# SPLED-01.net
KiCad netlist of a schematic drawn in EAGLE
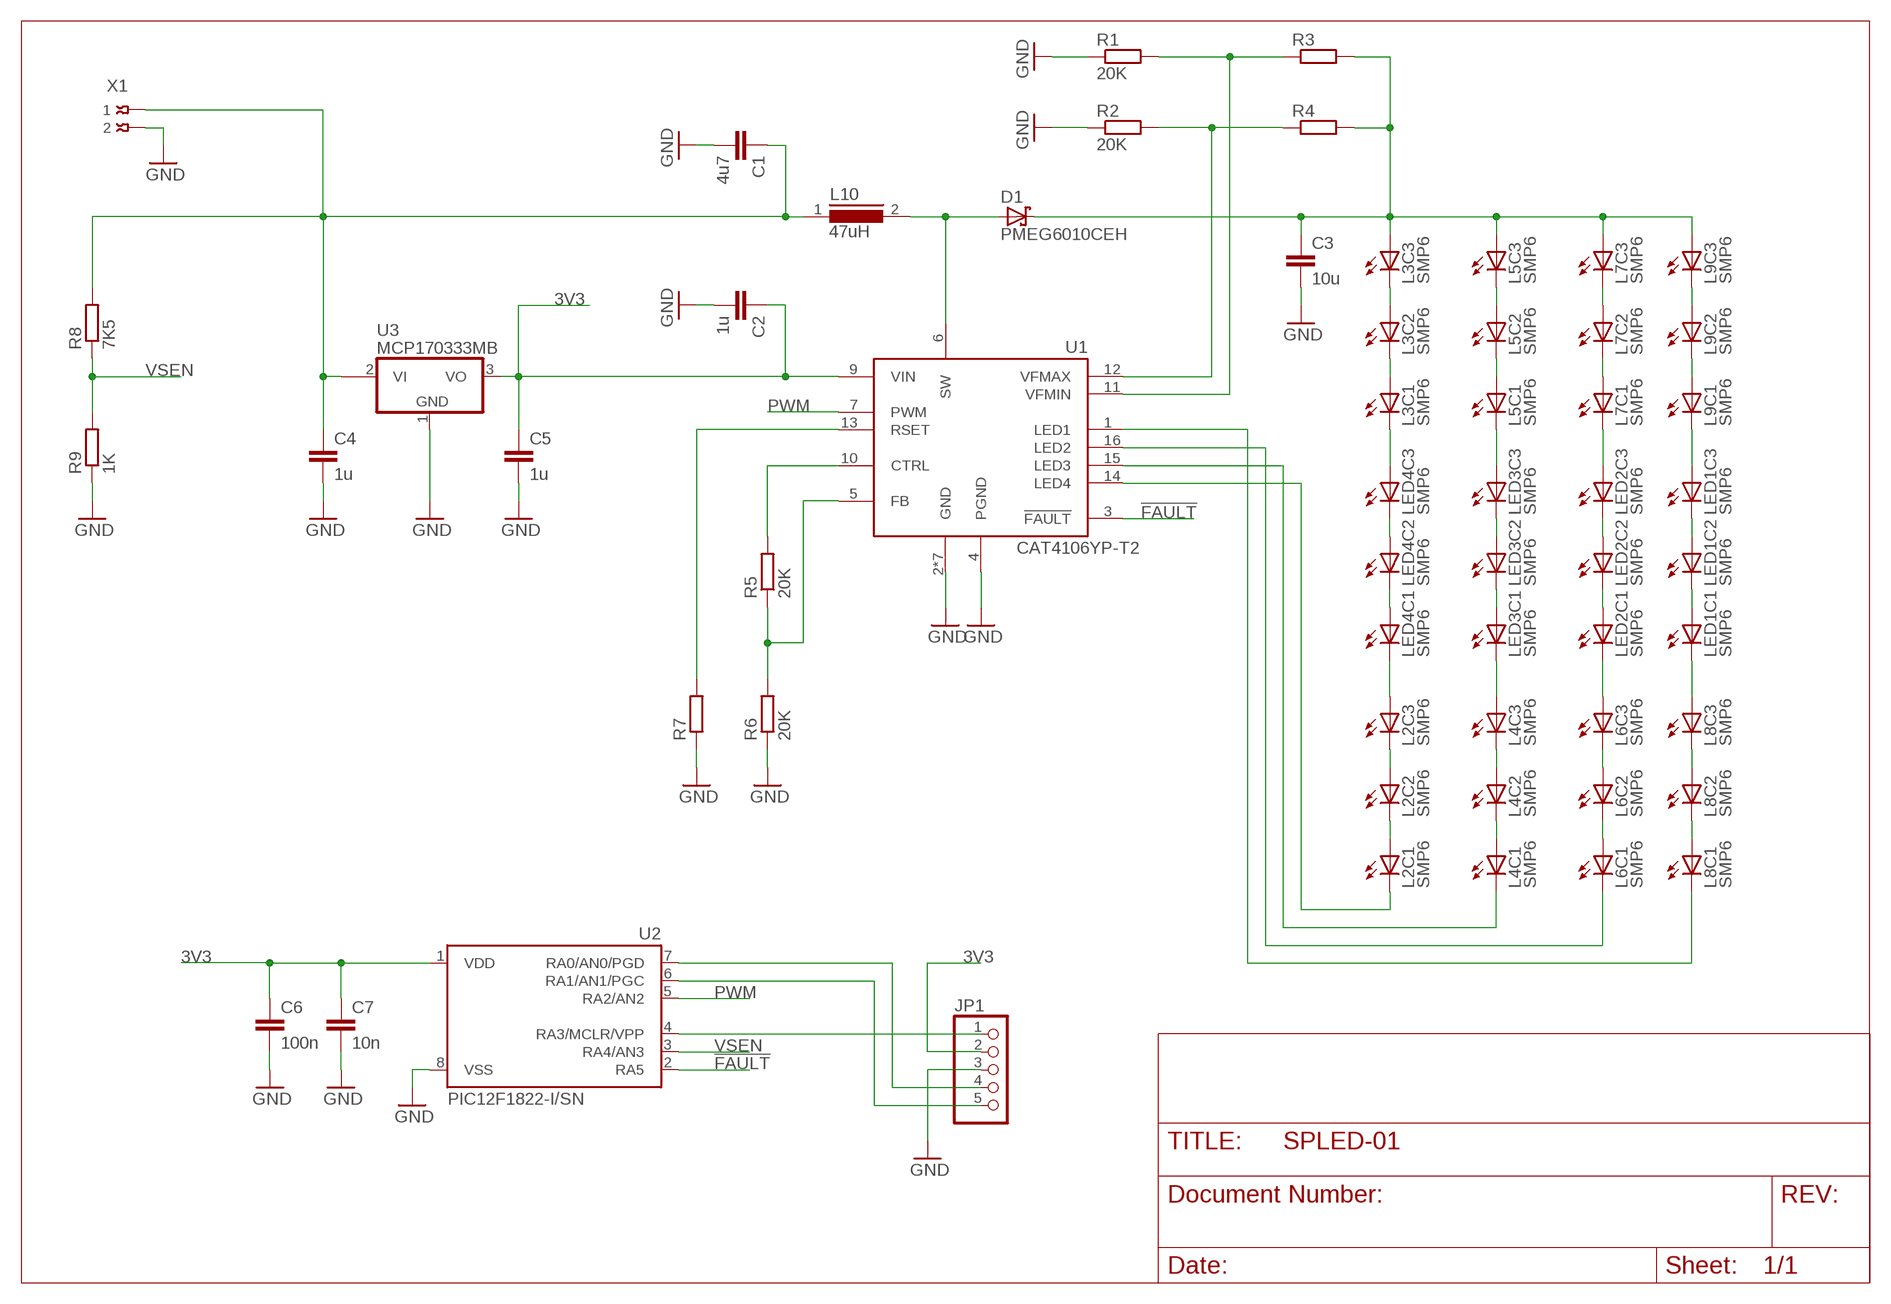
[diagram p0: schematic, sheet 1]

(export (version "E")
  (design (tool "Eeschema 10.0.6"))
  (components
    (comp (ref "C1")
      (value "4u7")
      (footprint "eagle-import:C1206K")
      (libsource (lib "eagle-import") (part "C-EUC1206K"))
    )
    (comp (ref "C2")
      (value "1u")
      (footprint "eagle-import:C1206K")
      (libsource (lib "eagle-import") (part "C-EUC1206K"))
    )
    (comp (ref "C3")
      (value "10u")
      (footprint "eagle-import:C1206K")
      (libsource (lib "eagle-import") (part "C-EUC1206K"))
    )
    (comp (ref "C4")
      (value "1u")
      (footprint "eagle-import:C1206K")
      (libsource (lib "eagle-import") (part "C-EUC1206K"))
    )
    (comp (ref "C5")
      (value "1u")
      (footprint "eagle-import:C1206K")
      (libsource (lib "eagle-import") (part "C-EUC1206K"))
    )
    (comp (ref "C6")
      (value "100n")
      (footprint "eagle-import:C1206K")
      (libsource (lib "eagle-import") (part "C-EUC1206K"))
    )
    (comp (ref "C7")
      (value "10n")
      (footprint "eagle-import:C1206K")
      (libsource (lib "eagle-import") (part "C-EUC1206K"))
    )
    (comp (ref "D1")
      (value "PMEG6010CEH")
      (footprint "eagle-import:SOD123FL")
      (libsource (lib "eagle-import") (part "SMF5.0AT1"))
    )
    (comp (ref "JP1")
      (value "PINHD-1X5-2MM")
      (footprint "eagle-import:1X05-2MM")
      (libsource (lib "eagle-import") (part "PINHD-1X5-2MM"))
    )
    (comp (ref "L2")
      (value "SMP6")
      (footprint "eagle-import:PLCC6")
      (libsource (lib "eagle-import") (part "SMP6"))
    )
    (comp (ref "L3")
      (value "SMP6")
      (footprint "eagle-import:PLCC6")
      (libsource (lib "eagle-import") (part "SMP6"))
    )
    (comp (ref "L4")
      (value "SMP6")
      (footprint "eagle-import:PLCC6")
      (libsource (lib "eagle-import") (part "SMP6"))
    )
    (comp (ref "L5")
      (value "SMP6")
      (footprint "eagle-import:PLCC6")
      (libsource (lib "eagle-import") (part "SMP6"))
    )
    (comp (ref "L6")
      (value "SMP6")
      (footprint "eagle-import:PLCC6")
      (libsource (lib "eagle-import") (part "SMP6"))
    )
    (comp (ref "L7")
      (value "SMP6")
      (footprint "eagle-import:PLCC6")
      (libsource (lib "eagle-import") (part "SMP6"))
    )
    (comp (ref "L8")
      (value "SMP6")
      (footprint "eagle-import:PLCC6")
      (libsource (lib "eagle-import") (part "SMP6"))
    )
    (comp (ref "L9")
      (value "SMP6")
      (footprint "eagle-import:PLCC6")
      (libsource (lib "eagle-import") (part "SMP6"))
    )
    (comp (ref "L10")
      (value "47uH")
      (footprint "eagle-import:DR73")
      (libsource (lib "eagle-import") (part "DR73"))
    )
    (comp (ref "LED1")
      (value "SMP6")
      (footprint "eagle-import:PLCC6")
      (libsource (lib "eagle-import") (part "SMP6"))
    )
    (comp (ref "LED2")
      (value "SMP6")
      (footprint "eagle-import:PLCC6")
      (libsource (lib "eagle-import") (part "SMP6"))
    )
    (comp (ref "LED3")
      (value "SMP6")
      (footprint "eagle-import:PLCC6")
      (libsource (lib "eagle-import") (part "SMP6"))
    )
    (comp (ref "LED4")
      (value "SMP6")
      (footprint "eagle-import:PLCC6")
      (libsource (lib "eagle-import") (part "SMP6"))
    )
    (comp (ref "R1")
      (value "20K")
      (footprint "eagle-import:R1206")
      (libsource (lib "eagle-import") (part "R-EU_R1206"))
    )
    (comp (ref "R2")
      (value "20K")
      (footprint "eagle-import:R1206")
      (libsource (lib "eagle-import") (part "R-EU_R1206"))
    )
    (comp (ref "R3")
      (value "R-EU_R1206")
      (footprint "eagle-import:R1206")
      (libsource (lib "eagle-import") (part "R-EU_R1206"))
    )
    (comp (ref "R4")
      (value "R-EU_R1206")
      (footprint "eagle-import:R1206")
      (libsource (lib "eagle-import") (part "R-EU_R1206"))
    )
    (comp (ref "R5")
      (value "20K")
      (footprint "eagle-import:R1206")
      (libsource (lib "eagle-import") (part "R-EU_R1206"))
    )
    (comp (ref "R6")
      (value "20K")
      (footprint "eagle-import:R1206")
      (libsource (lib "eagle-import") (part "R-EU_R1206"))
    )
    (comp (ref "R7")
      (value "R-EU_R1206")
      (footprint "eagle-import:R1206")
      (libsource (lib "eagle-import") (part "R-EU_R1206"))
    )
    (comp (ref "R8")
      (value "7K5")
      (footprint "eagle-import:R1206")
      (libsource (lib "eagle-import") (part "R-EU_R1206"))
    )
    (comp (ref "R9")
      (value "1K")
      (footprint "eagle-import:R1206")
      (libsource (lib "eagle-import") (part "R-EU_R1206"))
    )
    (comp (ref "U1")
      (value "CAT4106YP-T2")
      (footprint "eagle-import:TSSOP16")
      (libsource (lib "eagle-import") (part "CAT4106YP-T2"))
    )
    (comp (ref "U2")
      (value "PIC12F1822-I/SN")
      (footprint "eagle-import:SO08")
      (libsource (lib "eagle-import") (part "PIC12F1822-I/SN"))
    )
    (comp (ref "U3")
      (value "MCP170333MB")
      (footprint "eagle-import:SOT89")
      (libsource (lib "eagle-import") (part "MCP1703MB33"))
    )
    (comp (ref "X1")
      (value "009176002")
      (footprint "eagle-import:009176002")
      (fields (field (name "MPN") "009176002001006"))
      (libsource (lib "eagle-import") (part "00917?0026"))
    )
  )
  (nets
    (net (code "1") (name "/3V3") (class "Default")
      (node (ref "C2") (pin "1") (pinfunction "1_1") (pintype "passive"))
      (node (ref "C5") (pin "1") (pinfunction "1_1") (pintype "passive"))
      (node (ref "C6") (pin "1") (pinfunction "1_1") (pintype "passive"))
      (node (ref "C7") (pin "1") (pinfunction "1_1") (pintype "passive"))
      (node (ref "JP1") (pin "2") (pinfunction "2_2") (pintype "passive"))
      (node (ref "U1") (pin "9") (pinfunction "VIN_9") (pintype "bidirectional"))
      (node (ref "U2") (pin "1") (pinfunction "VDD_1") (pintype "power_in"))
      (node (ref "U3") (pin "3") (pinfunction "VO_3") (pintype "passive"))
    )
    (net (code "2") (name "/PWM") (class "Default")
      (node (ref "U1") (pin "7") (pinfunction "PWM_7") (pintype "bidirectional"))
      (node (ref "U2") (pin "5") (pinfunction "RA2/AN2_5") (pintype "bidirectional"))
    )
    (net (code "3") (name "/VSEN") (class "Default")
      (node (ref "R8") (pin "1") (pinfunction "1_1") (pintype "passive"))
      (node (ref "R9") (pin "2") (pinfunction "2_2") (pintype "passive"))
      (node (ref "U2") (pin "3") (pinfunction "RA4/AN3_3") (pintype "bidirectional"))
    )
    (net (code "4") (name "/~{FAULT}") (class "Default")
      (node (ref "U1") (pin "3") (pinfunction "~{FAULT}_3") (pintype "bidirectional"))
      (node (ref "U2") (pin "2") (pinfunction "RA5_2") (pintype "bidirectional"))
    )
    (net (code "5") (name "GND") (class "Default")
      (node (ref "C1") (pin "2") (pinfunction "2_2") (pintype "passive"))
      (node (ref "C2") (pin "2") (pinfunction "2_2") (pintype "passive"))
      (node (ref "C3") (pin "2") (pinfunction "2_2") (pintype "passive"))
      (node (ref "C4") (pin "2") (pinfunction "2_2") (pintype "passive"))
      (node (ref "C5") (pin "2") (pinfunction "2_2") (pintype "passive"))
      (node (ref "C6") (pin "2") (pinfunction "2_2") (pintype "passive"))
      (node (ref "C7") (pin "2") (pinfunction "2_2") (pintype "passive"))
      (node (ref "JP1") (pin "3") (pinfunction "3_3") (pintype "passive"))
      (node (ref "R1") (pin "1") (pinfunction "1_1") (pintype "passive"))
      (node (ref "R2") (pin "1") (pinfunction "1_1") (pintype "passive"))
      (node (ref "R6") (pin "1") (pinfunction "1_1") (pintype "passive"))
      (node (ref "R7") (pin "1") (pinfunction "1_1") (pintype "passive"))
      (node (ref "R9") (pin "1") (pinfunction "1_1") (pintype "passive"))
      (node (ref "U1") (pin "2") (pinfunction "GND_2") (pintype "bidirectional"))
      (node (ref "U1") (pin "4") (pinfunction "PGND_4") (pintype "bidirectional"))
      (node (ref "U1") (pin "P$1") (pinfunction "GND_P$1") (pintype "bidirectional"))
      (node (ref "U1") (pin "P$2") (pinfunction "GND_P$2") (pintype "bidirectional"))
      (node (ref "U1") (pin "P$3") (pinfunction "GND_P$3") (pintype "bidirectional"))
      (node (ref "U1") (pin "P$4") (pinfunction "GND_P$4") (pintype "bidirectional"))
      (node (ref "U1") (pin "P$5") (pinfunction "GND_P$5") (pintype "bidirectional"))
      (node (ref "U1") (pin "P$6") (pinfunction "GND_P$6") (pintype "bidirectional"))
      (node (ref "U2") (pin "8") (pinfunction "VSS_8") (pintype "power_in"))
      (node (ref "U3") (pin "1") (pinfunction "GND_1") (pintype "passive"))
      (node (ref "X1") (pin "2") (pinfunction "2_2") (pintype "passive"))
    )
    (net (code "6") (name "Net-(L2A-A)") (class "Default")
      (node (ref "L2") (pin "2") (pinfunction "A_2") (pintype "passive"))
      (node (ref "L2") (pin "3") (pinfunction "C_3") (pintype "passive"))
    )
    (net (code "7") (name "Net-(L2A-C)") (class "Default")
      (node (ref "L2") (pin "1") (pinfunction "C_1") (pintype "passive"))
      (node (ref "U1") (pin "14") (pinfunction "LED4_14") (pintype "bidirectional"))
    )
    (net (code "8") (name "Net-(L2B-A)") (class "Default")
      (node (ref "L2") (pin "4") (pinfunction "A_4") (pintype "passive"))
      (node (ref "L2") (pin "5") (pinfunction "C_5") (pintype "passive"))
    )
    (net (code "9") (name "Net-(L2C-A)") (class "Default")
      (node (ref "L2") (pin "6") (pinfunction "A_6") (pintype "passive"))
      (node (ref "LED4") (pin "1") (pinfunction "C_1") (pintype "passive"))
    )
    (net (code "10") (name "Net-(L3A-A)") (class "Default")
      (node (ref "L3") (pin "2") (pinfunction "A_2") (pintype "passive"))
      (node (ref "L3") (pin "3") (pinfunction "C_3") (pintype "passive"))
    )
    (net (code "11") (name "Net-(L3A-C)") (class "Default")
      (node (ref "L3") (pin "1") (pinfunction "C_1") (pintype "passive"))
      (node (ref "LED4") (pin "6") (pinfunction "A_6") (pintype "passive"))
    )
    (net (code "12") (name "Net-(L3B-A)") (class "Default")
      (node (ref "L3") (pin "4") (pinfunction "A_4") (pintype "passive"))
      (node (ref "L3") (pin "5") (pinfunction "C_5") (pintype "passive"))
    )
    (net (code "13") (name "Net-(L3C-A)") (class "Default")
      (node (ref "C3") (pin "1") (pinfunction "1_1") (pintype "passive"))
      (node (ref "D1") (pin "C") (pinfunction "C_C") (pintype "passive"))
      (node (ref "L3") (pin "6") (pinfunction "A_6") (pintype "passive"))
      (node (ref "L5") (pin "6") (pinfunction "A_6") (pintype "passive"))
      (node (ref "L7") (pin "6") (pinfunction "A_6") (pintype "passive"))
      (node (ref "L9") (pin "6") (pinfunction "A_6") (pintype "passive"))
      (node (ref "R3") (pin "2") (pinfunction "2_2") (pintype "passive"))
      (node (ref "R4") (pin "2") (pinfunction "2_2") (pintype "passive"))
    )
    (net (code "14") (name "Net-(L4A-A)") (class "Default")
      (node (ref "L4") (pin "2") (pinfunction "A_2") (pintype "passive"))
      (node (ref "L4") (pin "3") (pinfunction "C_3") (pintype "passive"))
    )
    (net (code "15") (name "Net-(L4A-C)") (class "Default")
      (node (ref "L4") (pin "1") (pinfunction "C_1") (pintype "passive"))
      (node (ref "U1") (pin "15") (pinfunction "LED3_15") (pintype "bidirectional"))
    )
    (net (code "16") (name "Net-(L4B-A)") (class "Default")
      (node (ref "L4") (pin "4") (pinfunction "A_4") (pintype "passive"))
      (node (ref "L4") (pin "5") (pinfunction "C_5") (pintype "passive"))
    )
    (net (code "17") (name "Net-(L4C-A)") (class "Default")
      (node (ref "L4") (pin "6") (pinfunction "A_6") (pintype "passive"))
      (node (ref "LED3") (pin "1") (pinfunction "C_1") (pintype "passive"))
    )
    (net (code "18") (name "Net-(L5A-A)") (class "Default")
      (node (ref "L5") (pin "2") (pinfunction "A_2") (pintype "passive"))
      (node (ref "L5") (pin "3") (pinfunction "C_3") (pintype "passive"))
    )
    (net (code "19") (name "Net-(L5A-C)") (class "Default")
      (node (ref "L5") (pin "1") (pinfunction "C_1") (pintype "passive"))
      (node (ref "LED3") (pin "6") (pinfunction "A_6") (pintype "passive"))
    )
    (net (code "20") (name "Net-(L5B-A)") (class "Default")
      (node (ref "L5") (pin "4") (pinfunction "A_4") (pintype "passive"))
      (node (ref "L5") (pin "5") (pinfunction "C_5") (pintype "passive"))
    )
    (net (code "21") (name "Net-(L6A-A)") (class "Default")
      (node (ref "L6") (pin "2") (pinfunction "A_2") (pintype "passive"))
      (node (ref "L6") (pin "3") (pinfunction "C_3") (pintype "passive"))
    )
    (net (code "22") (name "Net-(L6A-C)") (class "Default")
      (node (ref "L6") (pin "1") (pinfunction "C_1") (pintype "passive"))
      (node (ref "U1") (pin "16") (pinfunction "LED2_16") (pintype "bidirectional"))
    )
    (net (code "23") (name "Net-(L6B-A)") (class "Default")
      (node (ref "L6") (pin "4") (pinfunction "A_4") (pintype "passive"))
      (node (ref "L6") (pin "5") (pinfunction "C_5") (pintype "passive"))
    )
    (net (code "24") (name "Net-(L6C-A)") (class "Default")
      (node (ref "L6") (pin "6") (pinfunction "A_6") (pintype "passive"))
      (node (ref "LED2") (pin "1") (pinfunction "C_1") (pintype "passive"))
    )
    (net (code "25") (name "Net-(L7A-A)") (class "Default")
      (node (ref "L7") (pin "2") (pinfunction "A_2") (pintype "passive"))
      (node (ref "L7") (pin "3") (pinfunction "C_3") (pintype "passive"))
    )
    (net (code "26") (name "Net-(L7A-C)") (class "Default")
      (node (ref "L7") (pin "1") (pinfunction "C_1") (pintype "passive"))
      (node (ref "LED2") (pin "6") (pinfunction "A_6") (pintype "passive"))
    )
    (net (code "27") (name "Net-(L7B-A)") (class "Default")
      (node (ref "L7") (pin "4") (pinfunction "A_4") (pintype "passive"))
      (node (ref "L7") (pin "5") (pinfunction "C_5") (pintype "passive"))
    )
    (net (code "28") (name "Net-(L8A-A)") (class "Default")
      (node (ref "L8") (pin "2") (pinfunction "A_2") (pintype "passive"))
      (node (ref "L8") (pin "3") (pinfunction "C_3") (pintype "passive"))
    )
    (net (code "29") (name "Net-(L8A-C)") (class "Default")
      (node (ref "L8") (pin "1") (pinfunction "C_1") (pintype "passive"))
      (node (ref "U1") (pin "1") (pinfunction "LED1_1") (pintype "bidirectional"))
    )
    (net (code "30") (name "Net-(L8B-A)") (class "Default")
      (node (ref "L8") (pin "4") (pinfunction "A_4") (pintype "passive"))
      (node (ref "L8") (pin "5") (pinfunction "C_5") (pintype "passive"))
    )
    (net (code "31") (name "Net-(L8C-A)") (class "Default")
      (node (ref "L8") (pin "6") (pinfunction "A_6") (pintype "passive"))
      (node (ref "LED1") (pin "1") (pinfunction "C_1") (pintype "passive"))
    )
    (net (code "32") (name "Net-(L9A-A)") (class "Default")
      (node (ref "L9") (pin "2") (pinfunction "A_2") (pintype "passive"))
      (node (ref "L9") (pin "3") (pinfunction "C_3") (pintype "passive"))
    )
    (net (code "33") (name "Net-(L9A-C)") (class "Default")
      (node (ref "L9") (pin "1") (pinfunction "C_1") (pintype "passive"))
      (node (ref "LED1") (pin "6") (pinfunction "A_6") (pintype "passive"))
    )
    (net (code "34") (name "Net-(L9B-A)") (class "Default")
      (node (ref "L9") (pin "4") (pinfunction "A_4") (pintype "passive"))
      (node (ref "L9") (pin "5") (pinfunction "C_5") (pintype "passive"))
    )
    (net (code "35") (name "Net-(LED1A-A)") (class "Default")
      (node (ref "LED1") (pin "2") (pinfunction "A_2") (pintype "passive"))
      (node (ref "LED1") (pin "3") (pinfunction "C_3") (pintype "passive"))
    )
    (net (code "36") (name "Net-(LED1B-A)") (class "Default")
      (node (ref "LED1") (pin "4") (pinfunction "A_4") (pintype "passive"))
      (node (ref "LED1") (pin "5") (pinfunction "C_5") (pintype "passive"))
    )
    (net (code "37") (name "Net-(LED2A-A)") (class "Default")
      (node (ref "LED2") (pin "2") (pinfunction "A_2") (pintype "passive"))
      (node (ref "LED2") (pin "3") (pinfunction "C_3") (pintype "passive"))
    )
    (net (code "38") (name "Net-(LED2B-A)") (class "Default")
      (node (ref "LED2") (pin "4") (pinfunction "A_4") (pintype "passive"))
      (node (ref "LED2") (pin "5") (pinfunction "C_5") (pintype "passive"))
    )
    (net (code "39") (name "Net-(LED3A-A)") (class "Default")
      (node (ref "LED3") (pin "2") (pinfunction "A_2") (pintype "passive"))
      (node (ref "LED3") (pin "3") (pinfunction "C_3") (pintype "passive"))
    )
    (net (code "40") (name "Net-(LED3B-A)") (class "Default")
      (node (ref "LED3") (pin "4") (pinfunction "A_4") (pintype "passive"))
      (node (ref "LED3") (pin "5") (pinfunction "C_5") (pintype "passive"))
    )
    (net (code "41") (name "Net-(LED4A-A)") (class "Default")
      (node (ref "LED4") (pin "2") (pinfunction "A_2") (pintype "passive"))
      (node (ref "LED4") (pin "3") (pinfunction "C_3") (pintype "passive"))
    )
    (net (code "42") (name "Net-(LED4B-A)") (class "Default")
      (node (ref "LED4") (pin "4") (pinfunction "A_4") (pintype "passive"))
      (node (ref "LED4") (pin "5") (pinfunction "C_5") (pintype "passive"))
    )
    (net (code "43") (name "Net-(U1-CTRL)") (class "Default")
      (node (ref "R5") (pin "2") (pinfunction "2_2") (pintype "passive"))
      (node (ref "U1") (pin "10") (pinfunction "CTRL_10") (pintype "bidirectional"))
    )
    (net (code "44") (name "Net-(U1-FB)") (class "Default")
      (node (ref "R5") (pin "1") (pinfunction "1_1") (pintype "passive"))
      (node (ref "R6") (pin "2") (pinfunction "2_2") (pintype "passive"))
      (node (ref "U1") (pin "5") (pinfunction "FB_5") (pintype "bidirectional"))
    )
    (net (code "45") (name "Net-(U1-RSET)") (class "Default")
      (node (ref "R7") (pin "2") (pinfunction "2_2") (pintype "passive"))
      (node (ref "U1") (pin "13") (pinfunction "RSET_13") (pintype "bidirectional"))
    )
    (net (code "46") (name "Net-(U1-SW)") (class "Default")
      (node (ref "D1") (pin "A") (pinfunction "A_A") (pintype "passive"))
      (node (ref "L10") (pin "2") (pinfunction "2_2") (pintype "passive"))
      (node (ref "U1") (pin "6") (pinfunction "SW_6") (pintype "bidirectional"))
    )
    (net (code "47") (name "Net-(U1-VFMAX)") (class "Default")
      (node (ref "R2") (pin "2") (pinfunction "2_2") (pintype "passive"))
      (node (ref "R4") (pin "1") (pinfunction "1_1") (pintype "passive"))
      (node (ref "U1") (pin "12") (pinfunction "VFMAX_12") (pintype "bidirectional"))
    )
    (net (code "48") (name "Net-(U1-VFMIN)") (class "Default")
      (node (ref "R1") (pin "2") (pinfunction "2_2") (pintype "passive"))
      (node (ref "R3") (pin "1") (pinfunction "1_1") (pintype "passive"))
      (node (ref "U1") (pin "11") (pinfunction "VFMIN_11") (pintype "bidirectional"))
    )
    (net (code "49") (name "Net-(U2-RA0{slash}AN0{slash}PGD)") (class "Default")
      (node (ref "JP1") (pin "4") (pinfunction "4_4") (pintype "passive"))
      (node (ref "U2") (pin "7") (pinfunction "RA0/AN0/PGD_7") (pintype "bidirectional"))
    )
    (net (code "50") (name "Net-(U2-RA1{slash}AN1{slash}PGC)") (class "Default")
      (node (ref "JP1") (pin "5") (pinfunction "5_5") (pintype "passive"))
      (node (ref "U2") (pin "6") (pinfunction "RA1/AN1/PGC_6") (pintype "bidirectional"))
    )
    (net (code "51") (name "Net-(U2-RA3{slash}MCLR{slash}VPP)") (class "Default")
      (node (ref "JP1") (pin "1") (pinfunction "1_1") (pintype "passive"))
      (node (ref "U2") (pin "4") (pinfunction "RA3/MCLR/VPP_4") (pintype "bidirectional"))
    )
    (net (code "52") (name "Net-(U3-VI1)") (class "Default")
      (node (ref "C1") (pin "1") (pinfunction "1_1") (pintype "passive"))
      (node (ref "C4") (pin "1") (pinfunction "1_1") (pintype "passive"))
      (node (ref "L10") (pin "1") (pinfunction "1_1") (pintype "passive"))
      (node (ref "R8") (pin "2") (pinfunction "2_2") (pintype "passive"))
      (node (ref "U3") (pin "2@1") (pinfunction "VI1_2@1") (pintype "input"))
      (node (ref "X1") (pin "1") (pinfunction "1_1") (pintype "passive"))
    )
    (net (code "53") (name "unconnected-(U3-VI-Pad2)") (class "Default")
      (node (ref "U3") (pin "2") (pinfunction "VI_2") (pintype "input"))
    )
  )
)
